# ghidorah9.net
KiCad netlist of a schematic drawn in EAGLE
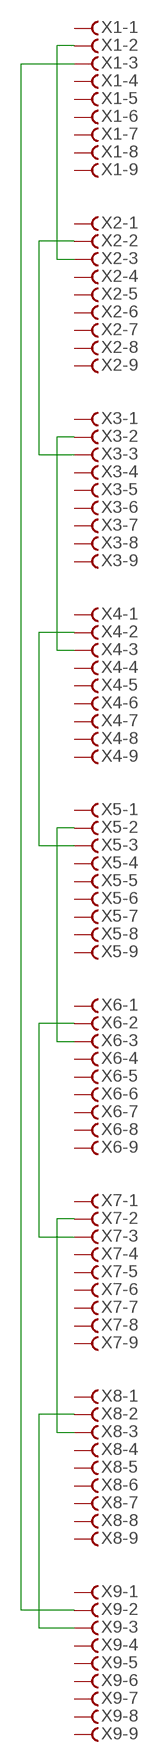
[diagram p0: schematic, sheet 1]

(export (version "E")
  (design (tool "Eeschema 10.0.6"))
  (components
    (comp (ref "X1")
      (value "F09DS")
      (footprint "eagle-import:F09D")
      (libsource (lib "eagle-import") (part "F09?SD"))
    )
    (comp (ref "X2")
      (value "F09DS")
      (footprint "eagle-import:F09D")
      (libsource (lib "eagle-import") (part "F09?SD"))
    )
    (comp (ref "X3")
      (value "F09DS")
      (footprint "eagle-import:F09D")
      (libsource (lib "eagle-import") (part "F09?SD"))
    )
    (comp (ref "X4")
      (value "F09DS")
      (footprint "eagle-import:F09D")
      (libsource (lib "eagle-import") (part "F09?SD"))
    )
    (comp (ref "X5")
      (value "F09DS")
      (footprint "eagle-import:F09D")
      (libsource (lib "eagle-import") (part "F09?SD"))
    )
    (comp (ref "X6")
      (value "F09DS")
      (footprint "eagle-import:F09D")
      (libsource (lib "eagle-import") (part "F09?SD"))
    )
    (comp (ref "X7")
      (value "F09DS")
      (footprint "eagle-import:F09D")
      (libsource (lib "eagle-import") (part "F09?SD"))
    )
    (comp (ref "X8")
      (value "F09DS")
      (footprint "eagle-import:F09D")
      (libsource (lib "eagle-import") (part "F09?SD"))
    )
    (comp (ref "X9")
      (value "F09VS")
      (footprint "eagle-import:F09V")
      (libsource (lib "eagle-import") (part "F09?SV"))
    )
  )
  (nets
    (net (code "1") (name "Net-(X1B-F)") (class "Default")
      (node (ref "X1") (pin "2") (pinfunction "F_2") (pintype "passive"))
      (node (ref "X2") (pin "3") (pinfunction "F_3") (pintype "passive"))
    )
    (net (code "2") (name "Net-(X1C-F)") (class "Default")
      (node (ref "X1") (pin "3") (pinfunction "F_3") (pintype "passive"))
      (node (ref "X9") (pin "2") (pinfunction "F_2") (pintype "passive"))
    )
    (net (code "3") (name "Net-(X2B-F)") (class "Default")
      (node (ref "X2") (pin "2") (pinfunction "F_2") (pintype "passive"))
      (node (ref "X3") (pin "3") (pinfunction "F_3") (pintype "passive"))
    )
    (net (code "4") (name "Net-(X3B-F)") (class "Default")
      (node (ref "X3") (pin "2") (pinfunction "F_2") (pintype "passive"))
      (node (ref "X4") (pin "3") (pinfunction "F_3") (pintype "passive"))
    )
    (net (code "5") (name "Net-(X4B-F)") (class "Default")
      (node (ref "X4") (pin "2") (pinfunction "F_2") (pintype "passive"))
      (node (ref "X5") (pin "3") (pinfunction "F_3") (pintype "passive"))
    )
    (net (code "6") (name "Net-(X5B-F)") (class "Default")
      (node (ref "X5") (pin "2") (pinfunction "F_2") (pintype "passive"))
      (node (ref "X6") (pin "3") (pinfunction "F_3") (pintype "passive"))
    )
    (net (code "7") (name "Net-(X6B-F)") (class "Default")
      (node (ref "X6") (pin "2") (pinfunction "F_2") (pintype "passive"))
      (node (ref "X7") (pin "3") (pinfunction "F_3") (pintype "passive"))
    )
    (net (code "8") (name "Net-(X7B-F)") (class "Default")
      (node (ref "X7") (pin "2") (pinfunction "F_2") (pintype "passive"))
      (node (ref "X8") (pin "3") (pinfunction "F_3") (pintype "passive"))
    )
    (net (code "9") (name "Net-(X8B-F)") (class "Default")
      (node (ref "X8") (pin "2") (pinfunction "F_2") (pintype "passive"))
      (node (ref "X9") (pin "3") (pinfunction "F_3") (pintype "passive"))
    )
    (net (code "10") (name "unconnected-(X1A-F-Pad1)") (class "Default")
      (node (ref "X1") (pin "1") (pinfunction "F_1") (pintype "passive"))
    )
    (net (code "11") (name "unconnected-(X1D-F-Pad4)") (class "Default")
      (node (ref "X1") (pin "4") (pinfunction "F_4") (pintype "passive"))
    )
    (net (code "12") (name "unconnected-(X1E-F-Pad5)") (class "Default")
      (node (ref "X1") (pin "5") (pinfunction "F_5") (pintype "passive"))
    )
    (net (code "13") (name "unconnected-(X1F-F-Pad6)") (class "Default")
      (node (ref "X1") (pin "6") (pinfunction "F_6") (pintype "passive"))
    )
    (net (code "14") (name "unconnected-(X1G-F-Pad7)") (class "Default")
      (node (ref "X1") (pin "7") (pinfunction "F_7") (pintype "passive"))
    )
    (net (code "15") (name "unconnected-(X1H-F-Pad8)") (class "Default")
      (node (ref "X1") (pin "8") (pinfunction "F_8") (pintype "passive"))
    )
    (net (code "16") (name "unconnected-(X1I-F-Pad9)") (class "Default")
      (node (ref "X1") (pin "9") (pinfunction "F_9") (pintype "passive"))
    )
    (net (code "17") (name "unconnected-(X2A-F-Pad1)") (class "Default")
      (node (ref "X2") (pin "1") (pinfunction "F_1") (pintype "passive"))
    )
    (net (code "18") (name "unconnected-(X2D-F-Pad4)") (class "Default")
      (node (ref "X2") (pin "4") (pinfunction "F_4") (pintype "passive"))
    )
    (net (code "19") (name "unconnected-(X2E-F-Pad5)") (class "Default")
      (node (ref "X2") (pin "5") (pinfunction "F_5") (pintype "passive"))
    )
    (net (code "20") (name "unconnected-(X2F-F-Pad6)") (class "Default")
      (node (ref "X2") (pin "6") (pinfunction "F_6") (pintype "passive"))
    )
    (net (code "21") (name "unconnected-(X2G-F-Pad7)") (class "Default")
      (node (ref "X2") (pin "7") (pinfunction "F_7") (pintype "passive"))
    )
    (net (code "22") (name "unconnected-(X2H-F-Pad8)") (class "Default")
      (node (ref "X2") (pin "8") (pinfunction "F_8") (pintype "passive"))
    )
    (net (code "23") (name "unconnected-(X2I-F-Pad9)") (class "Default")
      (node (ref "X2") (pin "9") (pinfunction "F_9") (pintype "passive"))
    )
    (net (code "24") (name "unconnected-(X3A-F-Pad1)") (class "Default")
      (node (ref "X3") (pin "1") (pinfunction "F_1") (pintype "passive"))
    )
    (net (code "25") (name "unconnected-(X3D-F-Pad4)") (class "Default")
      (node (ref "X3") (pin "4") (pinfunction "F_4") (pintype "passive"))
    )
    (net (code "26") (name "unconnected-(X3E-F-Pad5)") (class "Default")
      (node (ref "X3") (pin "5") (pinfunction "F_5") (pintype "passive"))
    )
    (net (code "27") (name "unconnected-(X3F-F-Pad6)") (class "Default")
      (node (ref "X3") (pin "6") (pinfunction "F_6") (pintype "passive"))
    )
    (net (code "28") (name "unconnected-(X3G-F-Pad7)") (class "Default")
      (node (ref "X3") (pin "7") (pinfunction "F_7") (pintype "passive"))
    )
    (net (code "29") (name "unconnected-(X3H-F-Pad8)") (class "Default")
      (node (ref "X3") (pin "8") (pinfunction "F_8") (pintype "passive"))
    )
    (net (code "30") (name "unconnected-(X3I-F-Pad9)") (class "Default")
      (node (ref "X3") (pin "9") (pinfunction "F_9") (pintype "passive"))
    )
    (net (code "31") (name "unconnected-(X4A-F-Pad1)") (class "Default")
      (node (ref "X4") (pin "1") (pinfunction "F_1") (pintype "passive"))
    )
    (net (code "32") (name "unconnected-(X4D-F-Pad4)") (class "Default")
      (node (ref "X4") (pin "4") (pinfunction "F_4") (pintype "passive"))
    )
    (net (code "33") (name "unconnected-(X4E-F-Pad5)") (class "Default")
      (node (ref "X4") (pin "5") (pinfunction "F_5") (pintype "passive"))
    )
    (net (code "34") (name "unconnected-(X4F-F-Pad6)") (class "Default")
      (node (ref "X4") (pin "6") (pinfunction "F_6") (pintype "passive"))
    )
    (net (code "35") (name "unconnected-(X4G-F-Pad7)") (class "Default")
      (node (ref "X4") (pin "7") (pinfunction "F_7") (pintype "passive"))
    )
    (net (code "36") (name "unconnected-(X4H-F-Pad8)") (class "Default")
      (node (ref "X4") (pin "8") (pinfunction "F_8") (pintype "passive"))
    )
    (net (code "37") (name "unconnected-(X4I-F-Pad9)") (class "Default")
      (node (ref "X4") (pin "9") (pinfunction "F_9") (pintype "passive"))
    )
    (net (code "38") (name "unconnected-(X5A-F-Pad1)") (class "Default")
      (node (ref "X5") (pin "1") (pinfunction "F_1") (pintype "passive"))
    )
    (net (code "39") (name "unconnected-(X5D-F-Pad4)") (class "Default")
      (node (ref "X5") (pin "4") (pinfunction "F_4") (pintype "passive"))
    )
    (net (code "40") (name "unconnected-(X5E-F-Pad5)") (class "Default")
      (node (ref "X5") (pin "5") (pinfunction "F_5") (pintype "passive"))
    )
    (net (code "41") (name "unconnected-(X5F-F-Pad6)") (class "Default")
      (node (ref "X5") (pin "6") (pinfunction "F_6") (pintype "passive"))
    )
    (net (code "42") (name "unconnected-(X5G-F-Pad7)") (class "Default")
      (node (ref "X5") (pin "7") (pinfunction "F_7") (pintype "passive"))
    )
    (net (code "43") (name "unconnected-(X5H-F-Pad8)") (class "Default")
      (node (ref "X5") (pin "8") (pinfunction "F_8") (pintype "passive"))
    )
    (net (code "44") (name "unconnected-(X5I-F-Pad9)") (class "Default")
      (node (ref "X5") (pin "9") (pinfunction "F_9") (pintype "passive"))
    )
    (net (code "45") (name "unconnected-(X6A-F-Pad1)") (class "Default")
      (node (ref "X6") (pin "1") (pinfunction "F_1") (pintype "passive"))
    )
    (net (code "46") (name "unconnected-(X6D-F-Pad4)") (class "Default")
      (node (ref "X6") (pin "4") (pinfunction "F_4") (pintype "passive"))
    )
    (net (code "47") (name "unconnected-(X6E-F-Pad5)") (class "Default")
      (node (ref "X6") (pin "5") (pinfunction "F_5") (pintype "passive"))
    )
    (net (code "48") (name "unconnected-(X6F-F-Pad6)") (class "Default")
      (node (ref "X6") (pin "6") (pinfunction "F_6") (pintype "passive"))
    )
    (net (code "49") (name "unconnected-(X6G-F-Pad7)") (class "Default")
      (node (ref "X6") (pin "7") (pinfunction "F_7") (pintype "passive"))
    )
    (net (code "50") (name "unconnected-(X6H-F-Pad8)") (class "Default")
      (node (ref "X6") (pin "8") (pinfunction "F_8") (pintype "passive"))
    )
    (net (code "51") (name "unconnected-(X6I-F-Pad9)") (class "Default")
      (node (ref "X6") (pin "9") (pinfunction "F_9") (pintype "passive"))
    )
    (net (code "52") (name "unconnected-(X7A-F-Pad1)") (class "Default")
      (node (ref "X7") (pin "1") (pinfunction "F_1") (pintype "passive"))
    )
    (net (code "53") (name "unconnected-(X7D-F-Pad4)") (class "Default")
      (node (ref "X7") (pin "4") (pinfunction "F_4") (pintype "passive"))
    )
    (net (code "54") (name "unconnected-(X7E-F-Pad5)") (class "Default")
      (node (ref "X7") (pin "5") (pinfunction "F_5") (pintype "passive"))
    )
    (net (code "55") (name "unconnected-(X7F-F-Pad6)") (class "Default")
      (node (ref "X7") (pin "6") (pinfunction "F_6") (pintype "passive"))
    )
    (net (code "56") (name "unconnected-(X7G-F-Pad7)") (class "Default")
      (node (ref "X7") (pin "7") (pinfunction "F_7") (pintype "passive"))
    )
    (net (code "57") (name "unconnected-(X7H-F-Pad8)") (class "Default")
      (node (ref "X7") (pin "8") (pinfunction "F_8") (pintype "passive"))
    )
    (net (code "58") (name "unconnected-(X7I-F-Pad9)") (class "Default")
      (node (ref "X7") (pin "9") (pinfunction "F_9") (pintype "passive"))
    )
    (net (code "59") (name "unconnected-(X8A-F-Pad1)") (class "Default")
      (node (ref "X8") (pin "1") (pinfunction "F_1") (pintype "passive"))
    )
    (net (code "60") (name "unconnected-(X8D-F-Pad4)") (class "Default")
      (node (ref "X8") (pin "4") (pinfunction "F_4") (pintype "passive"))
    )
    (net (code "61") (name "unconnected-(X8E-F-Pad5)") (class "Default")
      (node (ref "X8") (pin "5") (pinfunction "F_5") (pintype "passive"))
    )
    (net (code "62") (name "unconnected-(X8F-F-Pad6)") (class "Default")
      (node (ref "X8") (pin "6") (pinfunction "F_6") (pintype "passive"))
    )
    (net (code "63") (name "unconnected-(X8G-F-Pad7)") (class "Default")
      (node (ref "X8") (pin "7") (pinfunction "F_7") (pintype "passive"))
    )
    (net (code "64") (name "unconnected-(X8H-F-Pad8)") (class "Default")
      (node (ref "X8") (pin "8") (pinfunction "F_8") (pintype "passive"))
    )
    (net (code "65") (name "unconnected-(X8I-F-Pad9)") (class "Default")
      (node (ref "X8") (pin "9") (pinfunction "F_9") (pintype "passive"))
    )
    (net (code "66") (name "unconnected-(X9A-F-Pad1)") (class "Default")
      (node (ref "X9") (pin "1") (pinfunction "F_1") (pintype "passive"))
    )
    (net (code "67") (name "unconnected-(X9D-F-Pad4)") (class "Default")
      (node (ref "X9") (pin "4") (pinfunction "F_4") (pintype "passive"))
    )
    (net (code "68") (name "unconnected-(X9E-F-Pad5)") (class "Default")
      (node (ref "X9") (pin "5") (pinfunction "F_5") (pintype "passive"))
    )
    (net (code "69") (name "unconnected-(X9F-F-Pad6)") (class "Default")
      (node (ref "X9") (pin "6") (pinfunction "F_6") (pintype "passive"))
    )
    (net (code "70") (name "unconnected-(X9G-F-Pad7)") (class "Default")
      (node (ref "X9") (pin "7") (pinfunction "F_7") (pintype "passive"))
    )
    (net (code "71") (name "unconnected-(X9H-F-Pad8)") (class "Default")
      (node (ref "X9") (pin "8") (pinfunction "F_8") (pintype "passive"))
    )
    (net (code "72") (name "unconnected-(X9I-F-Pad9)") (class "Default")
      (node (ref "X9") (pin "9") (pinfunction "F_9") (pintype "passive"))
    )
  )
)
